# battery-balancer.net
KiCad netlist of a schematic drawn in Altium Designer
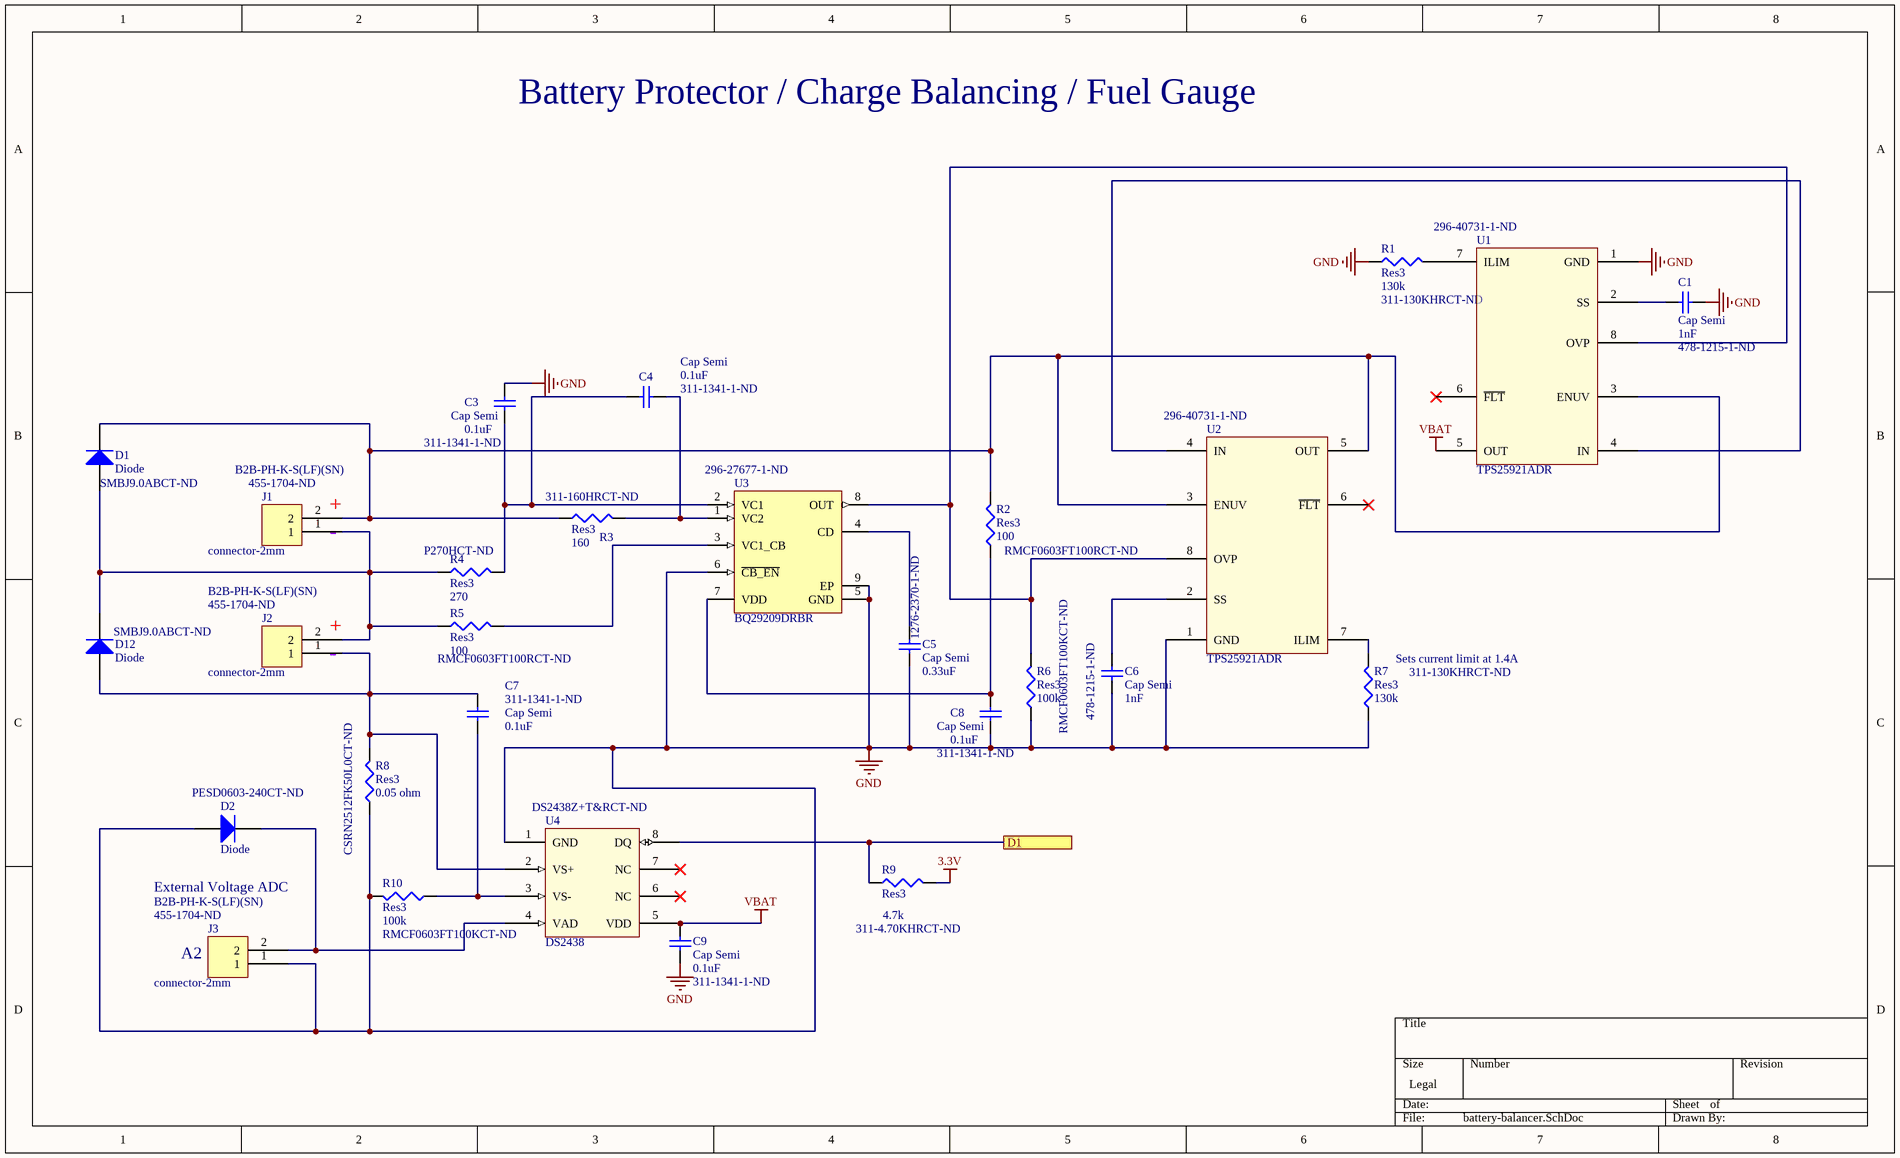
[diagram p0: battery-balancer.SchDoc]

(export (version "E")
  (design (tool "Eeschema 10.0.6"))
  (components
    (comp (ref "C1")
      (value "Cap Semi")
      (footprint "1608[0603]")
      (description "Capacitor (Semiconductor SIM Model)")
      (fields
        (field (name "ALTIUM_VALUE") "1nF")
        (field (name "SUPPLIER PART NUMBER 1") "478-1215-1-ND")
        (field (name "MANUFACTURER") "Kyocera AVX")
        (field (name "MANUFACTURER PART NUMBER") "06035C102KAT2A")
        (field (name "PUBLISHER") "Altium Limited")
      )
      (libsource (lib "Miscellaneous Devices") (part "Cap Semi"))
    )
    (comp (ref "C3")
      (value "Cap Semi")
      (footprint "1608[0603]")
      (description "Capacitor (Semiconductor SIM Model)")
      (fields
        (field (name "ALTIUM_VALUE") "0.1uF")
        (field (name "SUPPLIER PART NUMBER 1") "311-1341-1-ND")
        (field (name "MANUFACTURER") "Yageo")
        (field (name "MANUFACTURER PART NUMBER") "CC0603KRX7R8BB104")
        (field (name "PUBLISHER") "Altium Limited")
      )
      (libsource (lib "Miscellaneous Devices") (part "Cap Semi"))
    )
    (comp (ref "C4")
      (value "Cap Semi")
      (footprint "1608[0603]")
      (description "Capacitor (Semiconductor SIM Model)")
      (fields
        (field (name "ALTIUM_VALUE") "0.1uF")
        (field (name "SUPPLIER PART NUMBER 1") "311-1341-1-ND")
        (field (name "MANUFACTURER") "Yageo")
        (field (name "MANUFACTURER PART NUMBER") "CC0603KRX7R8BB104")
        (field (name "PUBLISHER") "Altium Limited")
      )
      (libsource (lib "Miscellaneous Devices") (part "Cap Semi"))
    )
    (comp (ref "C5")
      (value "Cap Semi")
      (footprint "1608[0603]")
      (description "Capacitor (Semiconductor SIM Model)")
      (fields
        (field (name "ALTIUM_VALUE") "0.33uF")
        (field (name "SUPPLIER PART NUMBER 1") "1276-2370-1-ND")
        (field (name "MANUFACTURER") "Samsung")
        (field (name "MANUFACTURER PART NUMBER") "CL10F334ZA8NNNC")
        (field (name "PUBLISHER") "Altium Limited")
      )
      (libsource (lib "Miscellaneous Devices") (part "Cap Semi"))
    )
    (comp (ref "C6")
      (value "Cap Semi")
      (footprint "1608[0603]")
      (description "Capacitor (Semiconductor SIM Model)")
      (fields
        (field (name "ALTIUM_VALUE") "1nF")
        (field (name "SUPPLIER PART NUMBER 1") "478-1215-1-ND")
        (field (name "MANUFACTURER") "Kyocera AVX")
        (field (name "MANUFACTURER PART NUMBER") "06035C102KAT2A")
        (field (name "PUBLISHER") "Altium Limited")
      )
      (libsource (lib "Miscellaneous Devices") (part "Cap Semi"))
    )
    (comp (ref "C7")
      (value "Cap Semi")
      (footprint "1608[0603]")
      (description "Capacitor (Semiconductor SIM Model)")
      (fields
        (field (name "ALTIUM_VALUE") "0.1uF")
        (field (name "SUPPLIER PART NUMBER 1") "311-1341-1-ND")
        (field (name "MANUFACTURER") "Yageo")
        (field (name "MANUFACTURER PART NUMBER") "CC0603KRX7R8BB104")
        (field (name "PUBLISHER") "Altium Limited")
      )
      (libsource (lib "Miscellaneous Devices") (part "Cap Semi"))
    )
    (comp (ref "C8")
      (value "Cap Semi")
      (footprint "1608[0603]")
      (description "Capacitor (Semiconductor SIM Model)")
      (fields
        (field (name "ALTIUM_VALUE") "0.1uF")
        (field (name "SUPPLIER PART NUMBER 1") "311-1341-1-ND")
        (field (name "MANUFACTURER") "Yageo")
        (field (name "MANUFACTURER PART NUMBER") "CC0603KRX7R8BB104")
        (field (name "PUBLISHER") "Altium Limited")
      )
      (libsource (lib "Miscellaneous Devices") (part "Cap Semi"))
    )
    (comp (ref "C9")
      (value "Cap Semi")
      (footprint "1608[0603]")
      (description "Capacitor (Semiconductor SIM Model)")
      (fields
        (field (name "ALTIUM_VALUE") "0.1uF")
        (field (name "SUPPLIER PART NUMBER 1") "311-1341-1-ND")
        (field (name "MANUFACTURER") "Yageo")
        (field (name "MANUFACTURER PART NUMBER") "CC0603KRX7R8BB104")
        (field (name "PUBLISHER") "Altium Limited")
      )
      (libsource (lib "Miscellaneous Devices") (part "Cap Semi"))
    )
    (comp (ref "D1")
      (value "Diode")
      (footprint "smbj")
      (description "Default Diode")
      (fields
        (field (name "SUPPLIER PART NUMBER 1") "SMBJ9.0ABCT-ND")
        (field (name "MANUFACTURER") "Bourns")
        (field (name "MANUFACTURER PART NUMBER") "SMBJ9.0A")
      )
      (libsource (lib "Miscellaneous Devices") (part "Diode"))
    )
    (comp (ref "D2")
      (value "Diode")
      (footprint "J1-0603")
      (description "Default Diode")
      (fields
        (field (name "SUPPLIER PART NUMBER 1") "PESD0603-240CT-ND")
        (field (name "MANUFACTURER") "Littelfuse")
        (field (name "MANUFACTURER PART NUMBER") "RF1256-000")
        (field (name "PUBLISHER") "Altium Limited")
      )
      (libsource (lib "Miscellaneous Devices") (part "Diode"))
    )
    (comp (ref "D12")
      (value "Diode")
      (footprint "smbj")
      (description "Default Diode")
      (fields
        (field (name "SUPPLIER PART NUMBER 1") "SMBJ9.0ABCT-ND")
        (field (name "MANUFACTURER") "Bourns")
        (field (name "MANUFACTURER PART NUMBER") "SMBJ9.0A")
      )
      (libsource (lib "Miscellaneous Devices") (part "Diode"))
    )
    (comp (ref "J1")
      (value "connector-2mm")
      (footprint "B2B-PH-K-S(LF)(SN)")
      (fields
        (field (name "SUPPLIER PART NUMBER 1") "455-1704-ND")
        (field (name "MANUFACTURER") "JST")
        (field (name "MANUFACTURER PART NUMBER") "B2B-PH-K-S(LF)(SN)")
      )
      (libsource (lib "jst") (part "connector-2mm"))
    )
    (comp (ref "J2")
      (value "connector-2mm")
      (footprint "B2B-PH-K-S(LF)(SN)")
      (fields
        (field (name "SUPPLIER PART NUMBER 1") "455-1704-ND")
        (field (name "MANUFACTURER") "JST")
        (field (name "MANUFACTURER PART NUMBER") "B2B-PH-K-S(LF)(SN)")
      )
      (libsource (lib "jst") (part "connector-2mm"))
    )
    (comp (ref "J3")
      (value "connector-2mm")
      (footprint "B2B-PH-K-S(LF)(SN)")
      (fields
        (field (name "SUPPLIER PART NUMBER 1") "455-1704-ND")
        (field (name "MANUFACTURER") "JST")
        (field (name "MANUFACTURER PART NUMBER") "B2B-PH-K-S(LF)(SN)")
      )
      (libsource (lib "jst") (part "connector-2mm"))
    )
    (comp (ref "R1")
      (value "Res3")
      (footprint "J1-0603")
      (description "Resistor")
      (fields
        (field (name "ALTIUM_VALUE") "130k")
        (field (name "SUPPLIER PART NUMBER 1") "311-130KHRCT-ND")
        (field (name "MANUFACTURER") "Yageo")
        (field (name "MANUFACTURER PART NUMBER") "RC0603FR-07130KL")
        (field (name "PUBLISHER") "Altium Limited")
      )
      (libsource (lib "Miscellaneous Devices") (part "Res3"))
    )
    (comp (ref "R2")
      (value "Res3")
      (footprint "J1-0603")
      (description "Resistor")
      (fields
        (field (name "ALTIUM_VALUE") "100")
        (field (name "SUPPLIER PART NUMBER 1") "RMCF0603FT100RCT-ND")
        (field (name "MANUFACTURER") "Stackpole Electronics")
        (field (name "MANUFACTURER PART NUMBER") "RMCF0603FT100R")
        (field (name "PUBLISHER") "Altium Limited")
      )
      (libsource (lib "Miscellaneous Devices") (part "Res3"))
    )
    (comp (ref "R3")
      (value "Res3")
      (footprint "J1-0603")
      (description "Resistor")
      (fields
        (field (name "ALTIUM_VALUE") "160")
        (field (name "SUPPLIER PART NUMBER 1") "311-160HRCT-ND")
        (field (name "MANUFACTURER") "Yageo")
        (field (name "MANUFACTURER PART NUMBER") "RC0603FR-07160RL")
        (field (name "PUBLISHER") "Altium Limited")
      )
      (libsource (lib "Miscellaneous Devices") (part "Res3"))
    )
    (comp (ref "R4")
      (value "Res3")
      (footprint "J1-0603")
      (description "Resistor")
      (fields
        (field (name "ALTIUM_VALUE") "270")
        (field (name "SUPPLIER PART NUMBER 1") "P270HCT-ND")
        (field (name "MANUFACTURER") "Panasonic")
        (field (name "MANUFACTURER PART NUMBER") "ERJ3EKF2700V")
        (field (name "PUBLISHER") "Altium Limited")
      )
      (libsource (lib "Miscellaneous Devices") (part "Res3"))
    )
    (comp (ref "R5")
      (value "Res3")
      (footprint "J1-0603")
      (description "Resistor")
      (fields
        (field (name "ALTIUM_VALUE") "100")
        (field (name "SUPPLIER PART NUMBER 1") "RMCF0603FT100RCT-ND")
        (field (name "MANUFACTURER") "Stackpole Electronics")
        (field (name "MANUFACTURER PART NUMBER") "RMCF0603FT100R")
        (field (name "PUBLISHER") "Altium Limited")
      )
      (libsource (lib "Miscellaneous Devices") (part "Res3"))
    )
    (comp (ref "R6")
      (value "Res3")
      (footprint "J1-0603")
      (description "Resistor")
      (fields
        (field (name "ALTIUM_VALUE") "100k")
        (field (name "SUPPLIER PART NUMBER 1") "RMCF0603FT100KCT-ND")
        (field (name "MANUFACTURER") "Stackpole Electronics")
        (field (name "MANUFACTURER PART NUMBER") "RMCF0603FT100K")
        (field (name "PUBLISHER") "Altium Limited")
      )
      (libsource (lib "Miscellaneous Devices") (part "Res3"))
    )
    (comp (ref "R7")
      (value "Res3")
      (footprint "J1-0603")
      (description "Resistor")
      (fields
        (field (name "ALTIUM_VALUE") "130k")
        (field (name "SUPPLIER PART NUMBER 1") "311-130KHRCT-ND")
        (field (name "MANUFACTURER") "Yageo")
        (field (name "MANUFACTURER PART NUMBER") "RC0603FR-07130KL")
        (field (name "PUBLISHER") "Altium Limited")
      )
      (libsource (lib "Miscellaneous Devices") (part "Res3"))
    )
    (comp (ref "R8")
      (value "Res3")
      (footprint "2512-resistor")
      (description "Res Thick Film 2512 0.05 Ohm 1% 2W ±200ppm/C Molded SMD Automotive T/R")
      (fields
        (field (name "ALTIUM_VALUE") "0.05 ohm")
        (field (name "SUPPLIER PART NUMBER 1") "CSRN2512FK50L0CT-ND")
        (field (name "MANUFACTURER") "Stackpole Electronics")
        (field (name "MANUFACTURER PART NUMBER") "CSRN2512FK50L0")
      )
      (libsource (lib "Miscellaneous Devices") (part "Res3"))
    )
    (comp (ref "R9")
      (value "Res3")
      (footprint "J1-0603")
      (description "Resistor")
      (fields
        (field (name "ALTIUM_VALUE") "4.7k")
        (field (name "SUPPLIER PART NUMBER 1") "311-4.70KHRCT-ND")
        (field (name "MANUFACTURER") "Yageo")
        (field (name "MANUFACTURER PART NUMBER") "RC0603FR-074K7L")
        (field (name "PUBLISHER") "Altium Limited")
      )
      (libsource (lib "Miscellaneous Devices") (part "Res3"))
    )
    (comp (ref "R10")
      (value "Res3")
      (footprint "J1-0603")
      (description "Resistor")
      (fields
        (field (name "ALTIUM_VALUE") "100k")
        (field (name "SUPPLIER PART NUMBER 1") "RMCF0603FT100KCT-ND")
        (field (name "MANUFACTURER") "Stackpole Electronics")
        (field (name "MANUFACTURER PART NUMBER") "RMCF0603FT100K")
        (field (name "PUBLISHER") "Altium Limited")
      )
      (libsource (lib "Miscellaneous Devices") (part "Res3"))
    )
    (comp (ref "U1")
      (value "TPS25921ADR")
      (footprint "D0008A_L")
      (description "IC PWR MGR EFUSE 18V 8SOIC")
      (fields
        (field (name "SUPPLIER PART NUMBER 1") "296-40731-1-ND")
        (field (name "MANUFACTURER") "Texas Instruments")
      )
      (libsource (lib "") (part "TPS25921ADR_1"))
    )
    (comp (ref "U2")
      (value "TPS25921ADR")
      (footprint "D0008A_L")
      (description "IC PWR MGR EFUSE 18V 8SOIC")
      (fields
        (field (name "SUPPLIER PART NUMBER 1") "296-40731-1-ND")
        (field (name "MANUFACTURER") "Texas Instruments")
      )
      (libsource (lib "ti") (part "TPS25921ADR"))
    )
    (comp (ref "U3")
      (value "BQ29209DRBR")
      (footprint "DRB0008B_V")
      (fields
        (field (name "MANUFACTURER") "Texas Instruments")
        (field (name "SUPPLIER PART NUMBER 1") "296-27677-1-ND")
      )
      (libsource (lib "Altium Content Vault") (part "TI-BQ29209DRB8-2400X1650TP"))
    )
    (comp (ref "U4")
      (value "DS2438")
      (footprint "21-0041B_8")
      (fields
        (field (name "SUPPLIER PART NUMBER 1") "DS2438Z+T&RCT-ND")
        (field (name "MANUFACTURER") "Maxim")
        (field (name "MANUFACTURER PART NUMBER") "DS2438Z+T&R")
      )
      (libsource (lib "maxim") (part "DS2438"))
    )
  )
  (nets
    (net (code "1") (name "/D1") (class "Default")
      (node (ref "R9") (pin "1") (pinfunction "1_1") (pintype "passive"))
      (node (ref "U4") (pin "8") (pinfunction "DQ_8") (pintype "bidirectional"))
    )
    (net (code "2") (name "3.3V") (class "Default")
      (node (ref "R9") (pin "2") (pinfunction "2_2") (pintype "passive"))
    )
    (net (code "3") (name "GND") (class "Default")
      (node (ref "C1") (pin "1") (pinfunction "1_1") (pintype "passive"))
      (node (ref "C3") (pin "2") (pinfunction "2_2") (pintype "passive"))
      (node (ref "C5") (pin "2") (pinfunction "2_2") (pintype "passive"))
      (node (ref "C6") (pin "1") (pinfunction "1_1") (pintype "passive"))
      (node (ref "C8") (pin "1") (pinfunction "1_1") (pintype "passive"))
      (node (ref "C9") (pin "2") (pinfunction "2_2") (pintype "passive"))
      (node (ref "D2") (pin "1") (pinfunction "A_1") (pintype "passive"))
      (node (ref "J3") (pin "1") (pinfunction "1_1") (pintype "passive"))
      (node (ref "R1") (pin "1") (pinfunction "1_1") (pintype "passive"))
      (node (ref "R10") (pin "2") (pinfunction "2_2") (pintype "passive"))
      (node (ref "R6") (pin "1") (pinfunction "1_1") (pintype "passive"))
      (node (ref "R7") (pin "1") (pinfunction "1_1") (pintype "passive"))
      (node (ref "R8") (pin "1") (pinfunction "1_1") (pintype "passive"))
      (node (ref "U1") (pin "1") (pinfunction "GND_1") (pintype "passive"))
      (node (ref "U2") (pin "1") (pinfunction "GND_1") (pintype "passive"))
      (node (ref "U3") (pin "5") (pinfunction "GND_5") (pintype "power_in"))
      (node (ref "U3") (pin "6") (pinfunction "~{CB_EN}_6") (pintype "input"))
      (node (ref "U3") (pin "9") (pinfunction "EP_9") (pintype "passive"))
      (node (ref "U4") (pin "1") (pinfunction "GND_1") (pintype "power_in"))
    )
    (net (code "4") (name "Net-(D1-A)") (class "Default")
      (node (ref "D1") (pin "1") (pinfunction "A_1") (pintype "passive"))
      (node (ref "D12") (pin "2") (pinfunction "K_2") (pintype "passive"))
      (node (ref "J1") (pin "1") (pinfunction "1_1") (pintype "passive"))
      (node (ref "J2") (pin "2") (pinfunction "2_2") (pintype "passive"))
      (node (ref "R4") (pin "1") (pinfunction "1_1") (pintype "passive"))
      (node (ref "R5") (pin "1") (pinfunction "1_1") (pintype "passive"))
    )
    (net (code "5") (name "Net-(D1-K)") (class "Default")
      (node (ref "D1") (pin "2") (pinfunction "K_2") (pintype "passive"))
      (node (ref "J1") (pin "2") (pinfunction "2_2") (pintype "passive"))
      (node (ref "R2") (pin "2") (pinfunction "2_2") (pintype "passive"))
      (node (ref "R3") (pin "1") (pinfunction "1_1") (pintype "passive"))
      (node (ref "U1") (pin "3") (pinfunction "ENUV_3") (pintype "passive"))
      (node (ref "U2") (pin "3") (pinfunction "ENUV_3") (pintype "passive"))
      (node (ref "U2") (pin "5") (pinfunction "OUT_5") (pintype "passive"))
    )
    (net (code "6") (name "Net-(D2-K)") (class "Default")
      (node (ref "D2") (pin "2") (pinfunction "K_2") (pintype "passive"))
      (node (ref "J3") (pin "2") (pinfunction "2_2") (pintype "passive"))
      (node (ref "U4") (pin "4") (pinfunction "VAD_4") (pintype "input"))
    )
    (net (code "7") (name "Net-(D12-A)") (class "Default")
      (node (ref "C7") (pin "2") (pinfunction "2_2") (pintype "passive"))
      (node (ref "D12") (pin "1") (pinfunction "A_1") (pintype "passive"))
      (node (ref "J2") (pin "1") (pinfunction "1_1") (pintype "passive"))
      (node (ref "R8") (pin "2") (pinfunction "2_2") (pintype "passive"))
      (node (ref "U4") (pin "2") (pinfunction "VS+_2") (pintype "input"))
    )
    (net (code "8") (name "Net-(U1-ILIM)") (class "Default")
      (node (ref "R1") (pin "2") (pinfunction "2_2") (pintype "passive"))
      (node (ref "U1") (pin "7") (pinfunction "ILIM_7") (pintype "passive"))
    )
    (net (code "9") (name "Net-(U1-IN)") (class "Default")
      (node (ref "U1") (pin "4") (pinfunction "IN_4") (pintype "passive"))
      (node (ref "U2") (pin "4") (pinfunction "IN_4") (pintype "passive"))
    )
    (net (code "10") (name "Net-(U1-OVP)") (class "Default")
      (node (ref "R6") (pin "2") (pinfunction "2_2") (pintype "passive"))
      (node (ref "U1") (pin "8") (pinfunction "OVP_8") (pintype "passive"))
      (node (ref "U2") (pin "8") (pinfunction "OVP_8") (pintype "passive"))
      (node (ref "U3") (pin "8") (pinfunction "OUT_8") (pintype "output"))
    )
    (net (code "11") (name "Net-(U1-SS)") (class "Default")
      (node (ref "C1") (pin "2") (pinfunction "2_2") (pintype "passive"))
      (node (ref "U1") (pin "2") (pinfunction "SS_2") (pintype "passive"))
    )
    (net (code "12") (name "Net-(U2-ILIM)") (class "Default")
      (node (ref "R7") (pin "2") (pinfunction "2_2") (pintype "passive"))
      (node (ref "U2") (pin "7") (pinfunction "ILIM_7") (pintype "passive"))
    )
    (net (code "13") (name "Net-(U2-SS)") (class "Default")
      (node (ref "C6") (pin "2") (pinfunction "2_2") (pintype "passive"))
      (node (ref "U2") (pin "2") (pinfunction "SS_2") (pintype "passive"))
    )
    (net (code "14") (name "Net-(U3-CD)") (class "Default")
      (node (ref "C5") (pin "1") (pinfunction "1_1") (pintype "passive"))
      (node (ref "U3") (pin "4") (pinfunction "CD_4") (pintype "passive"))
    )
    (net (code "15") (name "Net-(U3-VC1)") (class "Default")
      (node (ref "C3") (pin "1") (pinfunction "1_1") (pintype "passive"))
      (node (ref "C4") (pin "2") (pinfunction "2_2") (pintype "passive"))
      (node (ref "R4") (pin "2") (pinfunction "2_2") (pintype "passive"))
      (node (ref "U3") (pin "2") (pinfunction "VC1_2") (pintype "input"))
    )
    (net (code "16") (name "Net-(U3-VC1_CB)") (class "Default")
      (node (ref "R5") (pin "2") (pinfunction "2_2") (pintype "passive"))
      (node (ref "U3") (pin "3") (pinfunction "VC1_CB_3") (pintype "input"))
    )
    (net (code "17") (name "Net-(U3-VC2)") (class "Default")
      (node (ref "C4") (pin "1") (pinfunction "1_1") (pintype "passive"))
      (node (ref "R3") (pin "2") (pinfunction "2_2") (pintype "passive"))
      (node (ref "U3") (pin "1") (pinfunction "VC2_1") (pintype "input"))
    )
    (net (code "18") (name "Net-(U3-VDD)") (class "Default")
      (node (ref "C8") (pin "2") (pinfunction "2_2") (pintype "passive"))
      (node (ref "R2") (pin "1") (pinfunction "1_1") (pintype "passive"))
      (node (ref "U3") (pin "7") (pinfunction "VDD_7") (pintype "power_in"))
    )
    (net (code "19") (name "Net-(U4-VS-)") (class "Default")
      (node (ref "C7") (pin "1") (pinfunction "1_1") (pintype "passive"))
      (node (ref "R10") (pin "1") (pinfunction "1_1") (pintype "passive"))
      (node (ref "U4") (pin "3") (pinfunction "VS-_3") (pintype "input"))
    )
    (net (code "20") (name "VBAT") (class "Default")
      (node (ref "C9") (pin "1") (pinfunction "1_1") (pintype "passive"))
      (node (ref "U1") (pin "5") (pinfunction "OUT_5") (pintype "passive"))
      (node (ref "U4") (pin "5") (pinfunction "VDD_5") (pintype "passive"))
    )
    (net (code "21") (name "unconnected-(U1-~{FLT}-Pad6)") (class "Default")
      (node (ref "U1") (pin "6") (pinfunction "~{FLT}_6") (pintype "passive+no_connect"))
    )
    (net (code "22") (name "unconnected-(U2-~{FLT}-Pad6)") (class "Default")
      (node (ref "U2") (pin "6") (pinfunction "~{FLT}_6") (pintype "passive+no_connect"))
    )
    (net (code "23") (name "unconnected-(U4-NC-Pad6)") (class "Default")
      (node (ref "U4") (pin "6") (pinfunction "NC_6") (pintype "passive+no_connect"))
    )
    (net (code "24") (name "unconnected-(U4-NC-Pad7)") (class "Default")
      (node (ref "U4") (pin "7") (pinfunction "NC_7") (pintype "passive+no_connect"))
    )
  )
)
